# Power-2.net
KiCad netlist of a schematic drawn in Altium Designer
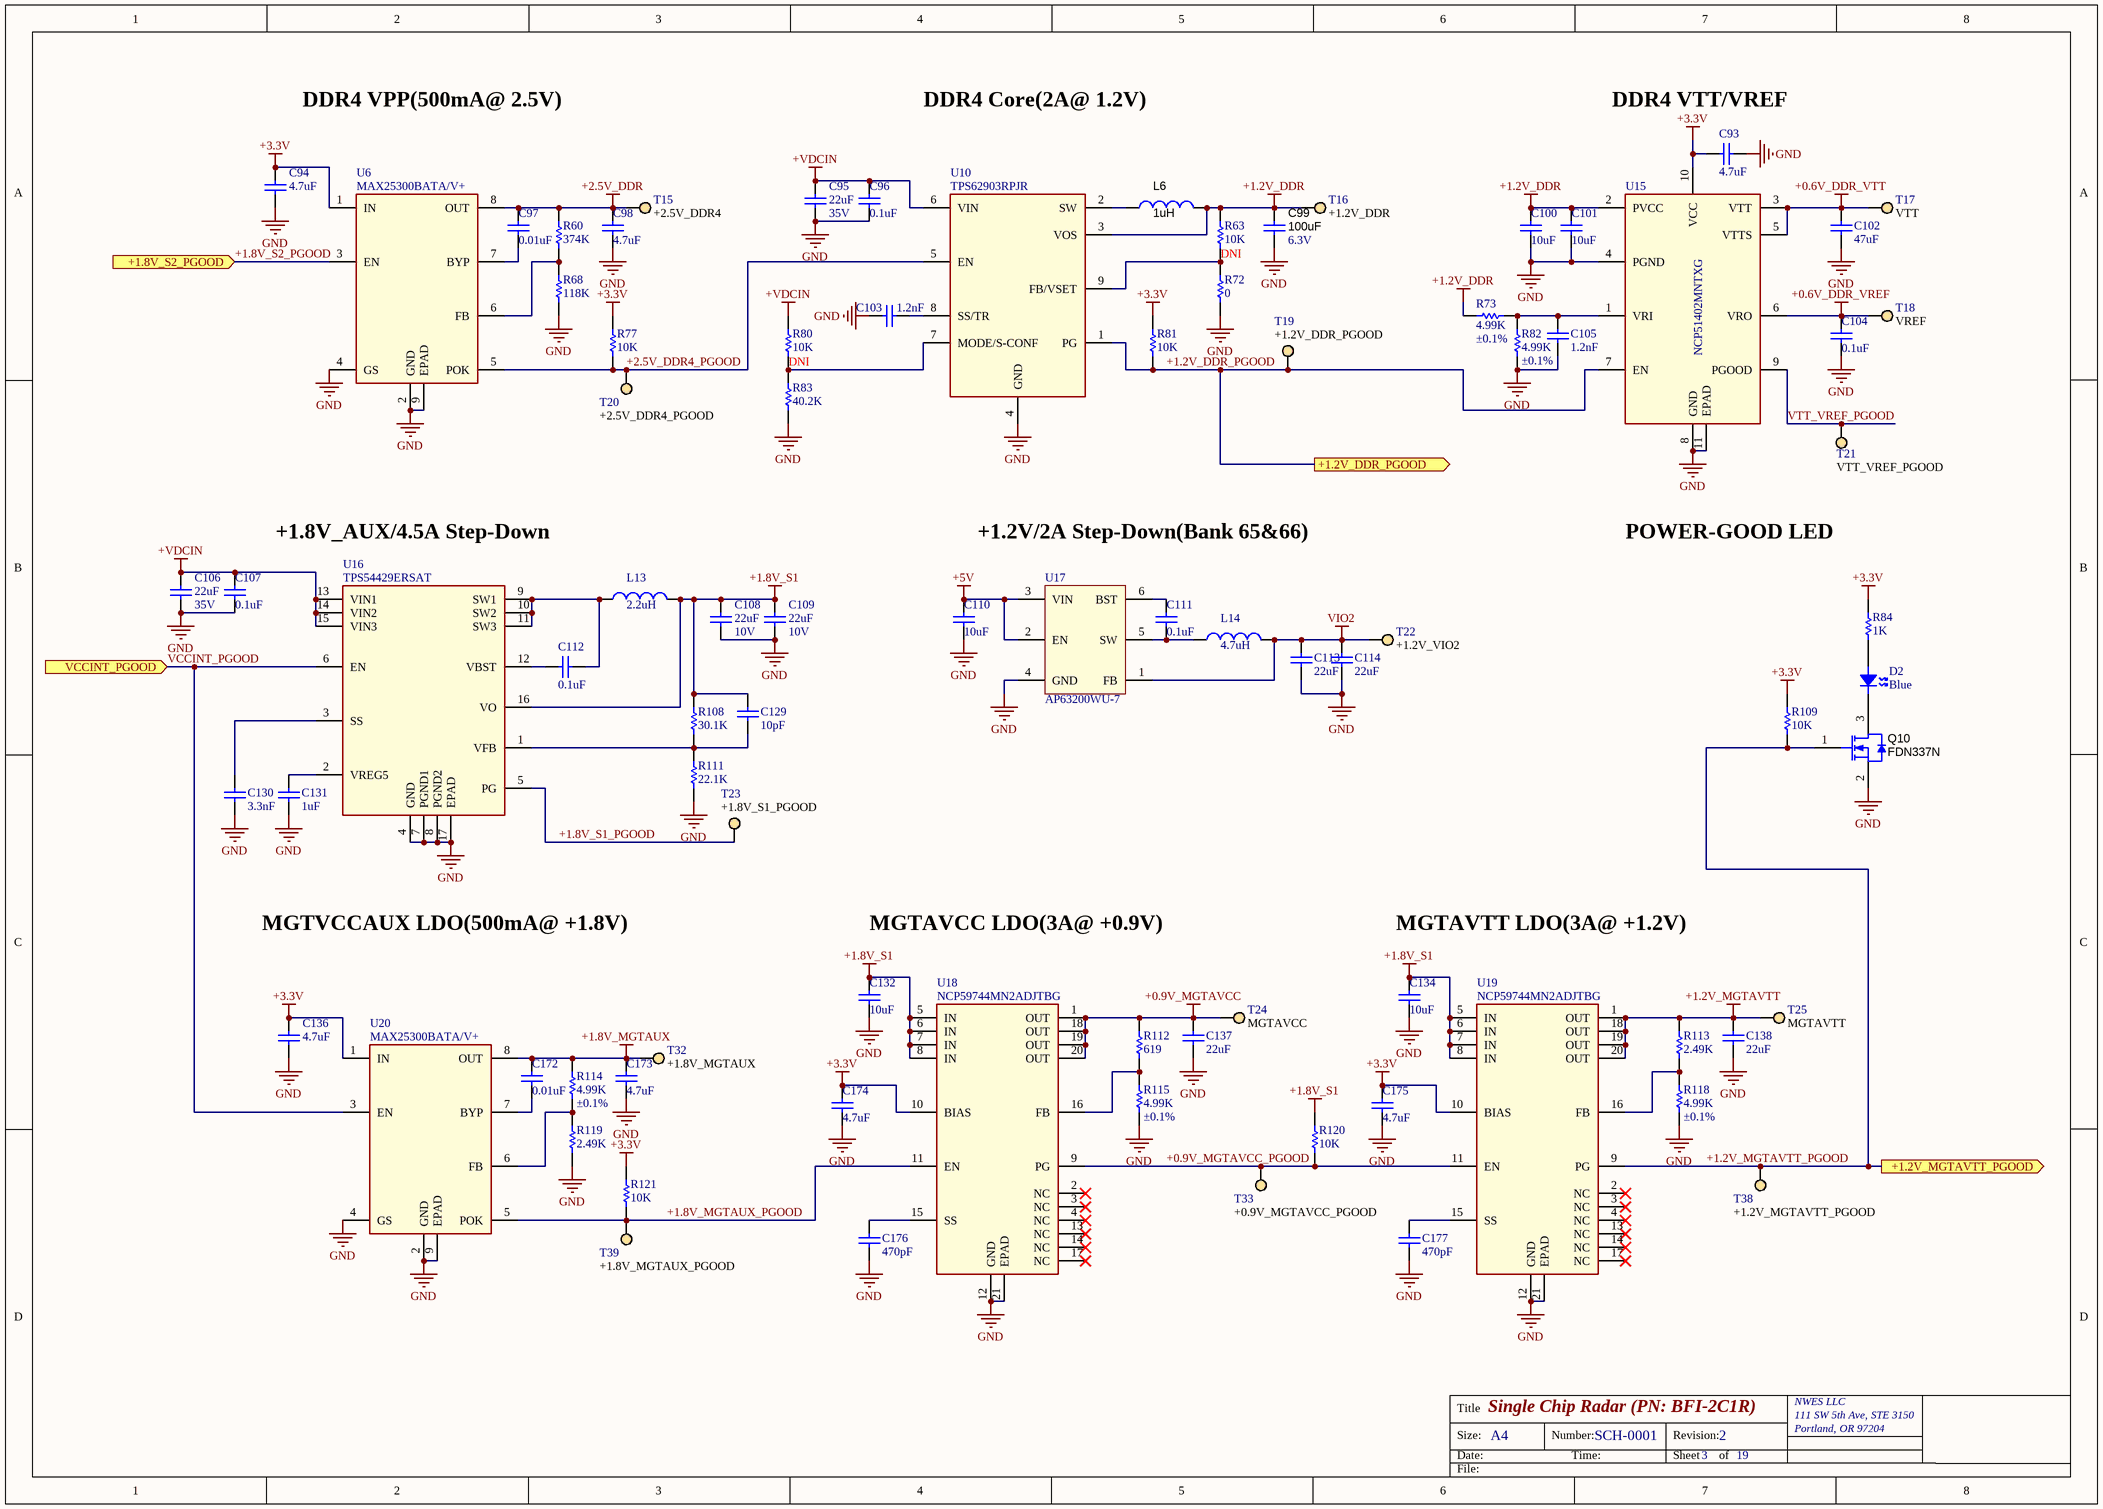
[diagram p0: Power-2.SchDoc]

(export (version "E")
  (design (tool "Eeschema 10.0.6"))
  (components
    (comp (ref "C93")
      (value "4.7uF")
      (footprint "CAPC1005X65USR")
      (description "CAP CER 4.7UF 10V X5R 0402")
      (fields
        (field (name "MANUFACTURER PART NUMBER") "C1005X5R1A475M050BC")
        (field (name "MANUFACTURER") "TDK Corporation")
      )
      (libsource (lib "Radar FPGA RF") (part "CAP CER 4.7UF 10V X5R 0402"))
    )
    (comp (ref "C94")
      (value "4.7uF")
      (footprint "CAPC1005X65USR")
      (description "CAP CER 4.7UF 10V X5R 0402")
      (fields
        (field (name "MANUFACTURER PART NUMBER") "C1005X5R1A475M050BC")
        (field (name "MANUFACTURER") "TDK Corporation")
      )
      (libsource (lib "Radar FPGA RF") (part "CAP CER 4.7UF 10V X5R 0402"))
    )
    (comp (ref "C95")
      (value "22uF")
      (footprint "CAP-1206")
      (description "C Series 1206 22 uF 35 V ±20 % Tolerance X5R SMT Multilayer Ceramic Capacitor")
      (fields
        (field (name "MANUFACTURER") "TDK")
        (field (name "MANUFACTURER PART NUMBER") "C3216X5R1V226M160AC")
        (field (name "VOLTAGE RATING") "35V")
      )
      (libsource (lib "Radar FPGA RF") (part "CAP CER 22UF 35V X5R 1206"))
    )
    (comp (ref "C96")
      (value "0.1uF")
      (footprint "CAPC1005X55USR")
      (description "CAP CER 0.1UF 25V X5R 0402")
      (fields
        (field (name "MANUFACTURER PART NUMBER") "CL05A104KA5NNNC")
        (field (name "MANUFACTURER") "Samsung Electro-Mechanics")
      )
      (libsource (lib "Radar FPGA RF") (part "CAP CER 0.1UF 25V X5R 0402"))
    )
    (comp (ref "C97")
      (value "0.01uF")
      (footprint "CAPC1005X55USR")
      (description "CAP CER 10000PF 50V X7R 0402")
      (fields
        (field (name "MANUFACTURER PART NUMBER") "GCM155R71H103KA55D")
        (field (name "MANUFACTURER") "Murata Electronics")
      )
      (libsource (lib "Radar FPGA RF") (part "CAP CER 0.01uF 50V X7R 0402"))
    )
    (comp (ref "C98")
      (value "4.7uF")
      (footprint "CAPC1005X65USR")
      (description "CAP CER 4.7UF 10V X5R 0402")
      (fields
        (field (name "MANUFACTURER PART NUMBER") "C1005X5R1A475M050BC")
        (field (name "MANUFACTURER") "TDK Corporation")
      )
      (libsource (lib "Radar FPGA RF") (part "CAP CER 4.7UF 10V X5R 0402"))
    )
    (comp (ref "C99")
      (value "100uF")
      (footprint "CAPC3216X180N")
      (description "1206 100 uF 6.3 V ±20% Tolerance X5R SMT Multilayer Ceramic Capacitor")
      (fields
        (field (name "MANUFACTURER") "Murata")
        (field (name "MANUFACTURER PART NUMBER") "GRM31CR60J107ME39L")
        (field (name "VOLTAGE RATING (DC)") "6.3V")
      )
      (libsource (lib "Radar FPGA RF") (part "CAP CER 100UF 6.3V X5R 1206"))
    )
    (comp (ref "C100")
      (value "10uF")
      (footprint "CAPC1005X90")
      (description "CAP CER 10UF 10V X5R 0402")
      (fields
        (field (name "MANUFACTURER PART NUMBER") "CL05A106MP8NUB8")
        (field (name "MANUFACTURER") "Samsung Electro-Mechanics")
      )
      (libsource (lib "Radar FPGA RF") (part "CAP CER 10UF 10V X5R 0402"))
    )
    (comp (ref "C101")
      (value "10uF")
      (footprint "CAPC1005X90")
      (description "CAP CER 10UF 10V X5R 0402")
      (fields
        (field (name "MANUFACTURER PART NUMBER") "CL05A106MP8NUB8")
        (field (name "MANUFACTURER") "Samsung Electro-Mechanics")
      )
      (libsource (lib "Radar FPGA RF") (part "CAP CER 10UF 10V X5R 0402"))
    )
    (comp (ref "C102")
      (value "47uF")
      (footprint "CAP-1206")
      (description "CAP CER 47UF 6.3V X5R 0805")
      (fields
        (field (name "MANUFACTURER") "Samsung")
        (field (name "MANUFACTURER PART NUMBER") "CL21A476MQYNNNE")
      )
      (libsource (lib "Radar FPGA RF") (part "CAP CER 47UF 6.3V X5R 0805"))
    )
    (comp (ref "C103")
      (value "1.2nF")
      (footprint "CAPC1005X55USR")
      (description "0402 1.2 nF 50 V ±10% Tolerance X7R SMT Multilayer Ceramic Capacitor")
      (fields
        (field (name "MANUFACTURER") "Murata")
        (field (name "MANUFACTURER PART NUMBER") "GRM155R71H122KA01D")
      )
      (libsource (lib "Radar FPGA RF") (part "CAP CER 1200PF 50V X7R 0402"))
    )
    (comp (ref "C104")
      (value "0.1uF")
      (footprint "CAPC1005X55USR")
      (description "CAP CER 0.1UF 25V X5R 0402")
      (fields
        (field (name "MANUFACTURER PART NUMBER") "CL05A104KA5NNNC")
        (field (name "MANUFACTURER") "Samsung Electro-Mechanics")
      )
      (libsource (lib "Radar FPGA RF") (part "CAP CER 0.1UF 25V X5R 0402"))
    )
    (comp (ref "C105")
      (value "1.2nF")
      (footprint "CAPC1005X55USR")
      (description "0402 1.2 nF 50 V ±10% Tolerance X7R SMT Multilayer Ceramic Capacitor")
      (fields
        (field (name "MANUFACTURER") "Murata")
        (field (name "MANUFACTURER PART NUMBER") "GRM155R71H122KA01D")
      )
      (libsource (lib "Radar FPGA RF") (part "CAP CER 1200PF 50V X7R 0402"))
    )
    (comp (ref "C106")
      (value "22uF")
      (footprint "CAPC3216X180N")
      (description "C Series 1206 22 uF 35 V ±20 % Tolerance X5R SMT Multilayer Ceramic Capacitor")
      (fields
        (field (name "MANUFACTURER") "TDK")
        (field (name "MANUFACTURER PART NUMBER") "C3216X5R1V226M160AC")
        (field (name "VOLTAGE RATING") "35V")
      )
      (libsource (lib "Radar FPGA RF") (part "CAP CER 22UF 35V X5R 1206"))
    )
    (comp (ref "C107")
      (value "0.1uF")
      (footprint "CAPC1005X55USR")
      (description "CAP CER 0.1UF 25V X5R 0402")
      (fields
        (field (name "MANUFACTURER PART NUMBER") "CL05A104KA5NNNC")
        (field (name "MANUFACTURER") "Samsung Electro-Mechanics")
      )
      (libsource (lib "Radar FPGA RF") (part "CAP CER 0.1UF 25V X5R 0402"))
    )
    (comp (ref "C108")
      (value "22uF")
      (footprint "CAPC1608X100N")
      (description "Multilayer Ceramic Capacitor, 22 uF, 10 V, ± 20%, X5R, 0603 [1608 Metric]")
      (fields
        (field (name "MANUFACTURER") "TDK")
        (field (name "MANUFACTURER PART NUMBER") "C1608X5R1A226M080AC")
        (field (name "VOLTAGE RATING") "10V")
      )
      (libsource (lib "Radar FPGA RF") (part "CAP CER 22UF 10V X5R 0603"))
    )
    (comp (ref "C109")
      (value "22uF")
      (footprint "CAPC1608X100N")
      (description "Multilayer Ceramic Capacitor, 22 uF, 10 V, ± 20%, X5R, 0603 [1608 Metric]")
      (fields
        (field (name "MANUFACTURER") "TDK")
        (field (name "MANUFACTURER PART NUMBER") "C1608X5R1A226M080AC")
        (field (name "VOLTAGE RATING") "10V")
      )
      (libsource (lib "Radar FPGA RF") (part "CAP CER 22UF 10V X5R 0603"))
    )
    (comp (ref "C110")
      (value "10uF")
      (footprint "CAPC1005X90")
      (description "CAP CER 10UF 10V X5R 0402")
      (fields
        (field (name "MANUFACTURER PART NUMBER") "CL05A106MP8NUB8")
        (field (name "MANUFACTURER") "Samsung Electro-Mechanics")
      )
      (libsource (lib "Radar FPGA RF") (part "CAP CER 10UF 10V X5R 0402"))
    )
    (comp (ref "C111")
      (value "0.1uF")
      (footprint "CAPC1005X55USR")
      (description "CAP CER 0.1UF 25V X5R 0402")
      (fields
        (field (name "MANUFACTURER PART NUMBER") "CL05A104KA5NNNC")
        (field (name "MANUFACTURER") "Samsung Electro-Mechanics")
      )
      (libsource (lib "Radar FPGA RF") (part "CAP CER 0.1UF 25V X5R 0402"))
    )
    (comp (ref "C112")
      (value "0.1uF")
      (footprint "CAPC1005X55USR")
      (description "CAP CER 0.1UF 25V X5R 0402")
      (fields
        (field (name "MANUFACTURER PART NUMBER") "CL05A104KA5NNNC")
        (field (name "MANUFACTURER") "Samsung Electro-Mechanics")
      )
      (libsource (lib "Radar FPGA RF") (part "CAP CER 0.1UF 25V X5R 0402"))
    )
    (comp (ref "C113")
      (value "22uF")
      (footprint "CAPC1608X100N")
      (description "Multilayer Ceramic Capacitor, 22 uF, 10 V, ± 20%, X5R, 0603 [1608 Metric]")
      (fields
        (field (name "MANUFACTURER") "TDK")
        (field (name "MANUFACTURER PART NUMBER") "C1608X5R1A226M080AC")
      )
      (libsource (lib "Radar FPGA RF") (part "CAP CER 22UF 10V X5R 0603"))
    )
    (comp (ref "C114")
      (value "22uF")
      (footprint "CAPC1608X100N")
      (description "Multilayer Ceramic Capacitor, 22 uF, 10 V, ± 20%, X5R, 0603 [1608 Metric]")
      (fields
        (field (name "MANUFACTURER") "TDK")
        (field (name "MANUFACTURER PART NUMBER") "C1608X5R1A226M080AC")
      )
      (libsource (lib "Radar FPGA RF") (part "CAP CER 22UF 10V X5R 0603"))
    )
    (comp (ref "C129")
      (value "10pF")
      (footprint "CAPC1005X55USR")
      (description "0402 10 pF 50 V ±5% Tolerance C0G SMT Multilayer Ceramic Capacitor")
      (fields
        (field (name "MANUFACTURER") "Murata")
        (field (name "MANUFACTURER PART NUMBER") "GRM1555C1H100JA01D")
      )
      (libsource (lib "Radar FPGA RF") (part "CAP CER 10PF 50V C0G/NP0 0402"))
    )
    (comp (ref "C130")
      (value "3.3nF")
      (footprint "CAPC1005X55USR")
      (description "0402 3.3 nF 50 V ±10% Tolerance X7R SMT Multilayer Ceramic Capacitor")
      (fields
        (field (name "MANUFACTURER") "Murata")
        (field (name "MANUFACTURER PART NUMBER") "GRM155R71H332KA01D")
      )
      (libsource (lib "Radar FPGA RF") (part "CAP CER 3300PF 50V X7R 0402"))
    )
    (comp (ref "C131")
      (value "1uF")
      (footprint "CAPC1005X55USR")
      (description "CAP CER 1UF 25V X5R 0402")
      (fields
        (field (name "MANUFACTURER PART NUMBER") "GRM155R61E105MA12D")
        (field (name "MANUFACTURER") "Murata Electronics")
      )
      (libsource (lib "Radar FPGA RF") (part "CAP CER 1UF 25V X5R 0402"))
    )
    (comp (ref "C132")
      (value "10uF")
      (footprint "CAPC1005X90")
      (description "CAP CER 10UF 10V X5R 0402")
      (fields
        (field (name "MANUFACTURER PART NUMBER") "CL05A106MP8NUB8")
        (field (name "MANUFACTURER") "Samsung Electro-Mechanics")
      )
      (libsource (lib "Radar FPGA RF") (part "CAP CER 10UF 10V X5R 0402"))
    )
    (comp (ref "C134")
      (value "10uF")
      (footprint "CAPC1005X90")
      (description "CAP CER 10UF 10V X5R 0402")
      (fields
        (field (name "MANUFACTURER PART NUMBER") "CL05A106MP8NUB8")
        (field (name "MANUFACTURER") "Samsung Electro-Mechanics")
      )
      (libsource (lib "Radar FPGA RF") (part "CAP CER 10UF 10V X5R 0402"))
    )
    (comp (ref "C136")
      (value "4.7uF")
      (footprint "CAPC1005X65USR")
      (description "CAP CER 4.7UF 10V X5R 0402")
      (fields
        (field (name "MANUFACTURER PART NUMBER") "C1005X5R1A475M050BC")
        (field (name "MANUFACTURER") "TDK Corporation")
      )
      (libsource (lib "Radar FPGA RF") (part "CAP CER 4.7UF 10V X5R 0402"))
    )
    (comp (ref "C137")
      (value "22uF")
      (footprint "CAPC1608X100N")
      (description "Multilayer Ceramic Capacitor, 22 uF, 10 V, ± 20%, X5R, 0603 [1608 Metric]")
      (fields
        (field (name "MANUFACTURER") "TDK")
        (field (name "MANUFACTURER PART NUMBER") "C1608X5R1A226M080AC")
      )
      (libsource (lib "Radar FPGA RF") (part "CAP CER 22UF 10V X5R 0603"))
    )
    (comp (ref "C138")
      (value "22uF")
      (footprint "CAPC1608X100N")
      (description "Multilayer Ceramic Capacitor, 22 uF, 10 V, ± 20%, X5R, 0603 [1608 Metric]")
      (fields
        (field (name "MANUFACTURER") "TDK")
        (field (name "MANUFACTURER PART NUMBER") "C1608X5R1A226M080AC")
      )
      (libsource (lib "Radar FPGA RF") (part "CAP CER 22UF 10V X5R 0603"))
    )
    (comp (ref "C172")
      (value "0.01uF")
      (footprint "CAPC1005X55USR")
      (description "CAP CER 10000PF 50V X7R 0402")
      (fields
        (field (name "MANUFACTURER PART NUMBER") "GCM155R71H103KA55D")
        (field (name "MANUFACTURER") "Murata Electronics")
      )
      (libsource (lib "Radar FPGA RF") (part "CAP CER 0.01uF 50V X7R 0402"))
    )
    (comp (ref "C173")
      (value "4.7uF")
      (footprint "CAPC1005X65USR")
      (description "CAP CER 4.7UF 10V X5R 0402")
      (fields
        (field (name "MANUFACTURER PART NUMBER") "C1005X5R1A475M050BC")
        (field (name "MANUFACTURER") "TDK Corporation")
      )
      (libsource (lib "Radar FPGA RF") (part "CAP CER 4.7UF 10V X5R 0402"))
    )
    (comp (ref "C174")
      (value "4.7uF")
      (footprint "CAPC1005X65USR")
      (description "CAP CER 4.7UF 10V X5R 0402")
      (fields
        (field (name "MANUFACTURER PART NUMBER") "C1005X5R1A475M050BC")
        (field (name "MANUFACTURER") "TDK Corporation")
      )
      (libsource (lib "Radar FPGA RF") (part "CAP CER 4.7UF 10V X5R 0402"))
    )
    (comp (ref "C175")
      (value "4.7uF")
      (footprint "CAPC1005X65USR")
      (description "CAP CER 4.7UF 10V X5R 0402")
      (fields
        (field (name "MANUFACTURER PART NUMBER") "C1005X5R1A475M050BC")
        (field (name "MANUFACTURER") "TDK Corporation")
      )
      (libsource (lib "Radar FPGA RF") (part "CAP CER 4.7UF 10V X5R 0402"))
    )
    (comp (ref "C176")
      (value "470pF")
      (footprint "CAPC1005X55USR")
      (fields
        (field (name "MANUFACTURER") "Murata")
        (field (name "MANUFACTURER PART NUMBER") "GRM155R71H471KA01D")
        (field (name "TOLERANCE") "10%")
      )
      (libsource (lib "Radar FPGA RF") (part "CAP CER 470PF 50V X7R 0402"))
    )
    (comp (ref "C177")
      (value "470pF")
      (footprint "CAPC1005X55USR")
      (fields
        (field (name "MANUFACTURER") "Murata")
        (field (name "MANUFACTURER PART NUMBER") "GRM155R71H471KA01D")
        (field (name "TOLERANCE") "10%")
      )
      (libsource (lib "Radar FPGA RF") (part "CAP CER 470PF 50V X7R 0402"))
    )
    (comp (ref "D2")
      (value "Blue")
      (footprint "LED_0603")
      (description "LED BLUE CLEAR 0603 SMD")
      (fields
        (field (name "MANUFACTURER") "Vishay Lite-On")
        (field (name "MANUFACTURER PART NUMBER") "LTST-C191TBKT")
      )
      (libsource (lib "Radar FPGA RF") (part "LED BLUE CLEAR CHIP SMD 0603"))
    )
    (comp (ref "L6")
      (value "1uH")
      (footprint "DFE252012P")
      (description "Inductor Power Chip Shielded Wirewound 1uH 20% 1MHz Metal 3.3A 0.04Ohm DCR 1008 T/R")
      (fields
        (field (name "MANUFACTURER") "Murata")
        (field (name "MANUFACTURER PART NUMBER") "DFE252012F-1R0M=P2")
      )
      (libsource (lib "Radar FPGA RF") (part "FIXED IND 1UH 3.3A 40 MOHM SMD"))
    )
    (comp (ref "L13")
      (value "2.2uH")
      (footprint "IND_SPM6530T-2R2M")
      (description "Inductor Power Shielded Wirewound 2.2uH 20% 100KHz Metal 8.2A 19mOhm DCR Blister T/R")
      (fields (field (name "MANUFACTURER") "TDK") (field (name "MANUFACTURER PART NUMBER") "SPM6530T-2R2M"))
      (libsource (lib "Radar FPGA RF") (part "FIXED IND 2.2UH 8.2A 19 MOHM SMD"))
    )
    (comp (ref "L14")
      (value "4.7uH")
      (footprint "DFE252012P")
      (description "FIXED IND 4.7UH 2A 200 MOHM SMD")
      (fields
        (field (name "MANUFACTURER") "Murata")
        (field (name "MANUFACTURER PART NUMBER") "DFE252012P-4R7M=P2")
      )
      (libsource (lib "Radar FPGA RF") (part "FIXED IND 4.7UH 2A 200 MOHM SMD"))
    )
    (comp (ref "Q10")
      (value "FDN337N")
      (footprint "SOT-23")
      (description "MOSFET N-CH 30V 2.2A SSOT3")
      (fields (field (name "MANUFACTURER") "ON Semiconductor / Fairchild"))
      (libsource (lib "Radar FPGA RF") (part "MOSFET N-CH 30V 2.2A SUPERSOT3"))
    )
    (comp (ref "R60")
      (value "374K")
      (footprint "RESC1005X40USR")
      (description "RES 374K OHM 1% 1/16W 0402")
      (fields
        (field (name "MANUFACTURER") "YAGEO")
        (field (name "MANUFACTURER PART NUMBER") "RC0402FR-07374KL")
      )
      (libsource (lib "Radar FPGA RF") (part "RES 374K OHM 1% 1/16W 0402"))
    )
    (comp (ref "R63")
      (value "10K")
      (footprint "RESC1005X40USR")
      (description "RES 10K OHM 1% 1/16W 0402")
      (fields
        (field (name "MANUFACTURER") "YAGEO")
        (field (name "MANUFACTURER PART NUMBER") "RC0402FR-0710KL")
      )
      (libsource (lib "Radar FPGA RF") (part "RES 10K OHM 1% 1/16W 0402"))
    )
    (comp (ref "R68")
      (value "118K")
      (footprint "RESC1005X40USR")
      (description "RES 118K OHM 1% 1/16W 0402")
      (fields
        (field (name "MANUFACTURER") "YAGEO")
        (field (name "MANUFACTURER PART NUMBER") "RC0402FR-07118KL")
      )
      (libsource (lib "Radar FPGA RF") (part "RES 118K OHM 1% 1/16W 0402"))
    )
    (comp (ref "R72")
      (value "0")
      (footprint "RESC1005X40USR")
      (description "RES 0 OHM JUMPER 1/16W 0402")
      (fields
        (field (name "MANUFACTURER") "Yageo")
        (field (name "MANUFACTURER PART NUMBER") "RC0402JR-070RL")
      )
      (libsource (lib "Radar FPGA RF") (part "RES 0 OHM JUMPER 1/16W 0402"))
    )
    (comp (ref "R73")
      (value "4.99K")
      (footprint "RESC1005X40USR")
      (description "RES SMD 4.99KOHM 0.1% 1/16W 0402")
      (fields
        (field (name "MANUFACTURER") "YAGEO")
        (field (name "MANUFACTURER PART NUMBER") "RT0402BRD074K99L")
        (field (name "TOLERANCE") "±0.1%")
      )
      (libsource (lib "Radar FPGA RF") (part "RES 4.99KOHM 0.1% 1/16W 0402"))
    )
    (comp (ref "R77")
      (value "10K")
      (footprint "RESC1005X40USR")
      (description "RES 10K OHM 1% 1/16W 0402")
      (fields
        (field (name "MANUFACTURER") "YAGEO")
        (field (name "MANUFACTURER PART NUMBER") "RC0402FR-0710KL")
      )
      (libsource (lib "Radar FPGA RF") (part "RES 10K OHM 1% 1/16W 0402"))
    )
    (comp (ref "R80")
      (value "10K")
      (footprint "RESC1005X40USR")
      (description "RES 10K OHM 1% 1/16W 0402")
      (fields
        (field (name "MANUFACTURER") "YAGEO")
        (field (name "MANUFACTURER PART NUMBER") "RC0402FR-0710KL")
      )
      (libsource (lib "Radar FPGA RF") (part "RES 10K OHM 1% 1/16W 0402"))
    )
    (comp (ref "R81")
      (value "10K")
      (footprint "RESC1005X40USR")
      (description "RES 10K OHM 1% 1/16W 0402")
      (fields
        (field (name "MANUFACTURER") "YAGEO")
        (field (name "MANUFACTURER PART NUMBER") "RC0402FR-0710KL")
      )
      (libsource (lib "Radar FPGA RF") (part "RES 10K OHM 1% 1/16W 0402"))
    )
    (comp (ref "R82")
      (value "4.99K")
      (footprint "RESC1005X40USR")
      (description "RES SMD 4.99KOHM 0.1% 1/16W 0402")
      (fields
        (field (name "MANUFACTURER") "YAGEO")
        (field (name "MANUFACTURER PART NUMBER") "RT0402BRD074K99L")
        (field (name "TOLERANCE") "±0.1%")
      )
      (libsource (lib "Radar FPGA RF") (part "RES 4.99KOHM 0.1% 1/16W 0402"))
    )
    (comp (ref "R83")
      (value "40.2K")
      (footprint "RESC1005X40USR")
      (description "RES 40.2K OHM 1% 1/16W 0402")
      (fields
        (field (name "MANUFACTURER") "YAGEO")
        (field (name "MANUFACTURER PART NUMBER") "RC0402FR-0740K2L")
      )
      (libsource (lib "Radar FPGA RF") (part "RES 40.2K OHM 1% 1/16W 0402"))
    )
    (comp (ref "R84")
      (value "1K")
      (footprint "RESC1005X40USR")
      (description "RES 1K OHM 1% 1/16W 0402")
      (fields
        (field (name "MANUFACTURER") "YAGEO")
        (field (name "MANUFACTURER PART NUMBER") "RC0402FR-071KL")
      )
      (libsource (lib "Radar FPGA RF") (part "RES 1K OHM 1% 1/16W 0402"))
    )
    (comp (ref "R108")
      (value "30.1K")
      (footprint "RESC1005X40USR")
      (description "RES 30.1K OHM 1% 1/16W 0402")
      (fields
        (field (name "MANUFACTURER") "YAGEO")
        (field (name "MANUFACTURER PART NUMBER") "RC0402FR-0730K1L")
      )
      (libsource (lib "Radar FPGA RF") (part "RES 30.1K OHM 1% 1/16W 0402"))
    )
    (comp (ref "R109")
      (value "10K")
      (footprint "RESC1005X40USR")
      (description "RES 10K OHM 1% 1/16W 0402")
      (fields
        (field (name "MANUFACTURER") "YAGEO")
        (field (name "MANUFACTURER PART NUMBER") "RC0402FR-0710KL")
      )
      (libsource (lib "Radar FPGA RF") (part "RES 10K OHM 1% 1/16W 0402"))
    )
    (comp (ref "R111")
      (value "22.1K")
      (footprint "RESC1005X40USR")
      (description "RES 22.1K OHM 1% 1/16W 0402")
      (fields
        (field (name "MANUFACTURER") "YAGEO")
        (field (name "MANUFACTURER PART NUMBER") "RC0402FR-0722K1L")
      )
      (libsource (lib "Radar FPGA RF") (part "RES 22.1K OHM 1% 1/16W 0402"))
    )
    (comp (ref "R112")
      (value "619")
      (footprint "RESC1005X40USR")
      (description "RES 619 OHM 1% 1/16W 0402")
      (fields
        (field (name "MANUFACTURER") "YAGEO")
        (field (name "MANUFACTURER PART NUMBER") "RC0402FR-07619RL")
      )
      (libsource (lib "Radar FPGA RF") (part "RES 619 OHM 1% 1/16W 0402"))
    )
    (comp (ref "R113")
      (value "2.49K")
      (footprint "RESC1005X40USR")
      (description "RES 2.49K OHM 1% 1/16W 0402")
      (fields
        (field (name "MANUFACTURER") "YAGEO")
        (field (name "MANUFACTURER PART NUMBER") "RC0402FR-072K49L")
      )
      (libsource (lib "Radar FPGA RF") (part "RES 2.49K OHM 1% 1/16W 0402"))
    )
    (comp (ref "R114")
      (value "4.99K")
      (footprint "RESC1005X40USR")
      (description "RES SMD 4.99KOHM 0.1% 1/16W 0402")
      (fields
        (field (name "MANUFACTURER") "YAGEO")
        (field (name "MANUFACTURER PART NUMBER") "RT0402BRD074K99L")
        (field (name "TOLERANCE") "±0.1%")
      )
      (libsource (lib "Radar FPGA RF") (part "RES 4.99KOHM 0.1% 1/16W 0402"))
    )
    (comp (ref "R115")
      (value "4.99K")
      (footprint "RESC1005X40USR")
      (description "RES SMD 4.99KOHM 0.1% 1/16W 0402")
      (fields
        (field (name "MANUFACTURER") "YAGEO")
        (field (name "MANUFACTURER PART NUMBER") "RT0402BRD074K99L")
        (field (name "TOLERANCE") "±0.1%")
      )
      (libsource (lib "Radar FPGA RF") (part "RES 4.99KOHM 0.1% 1/16W 0402"))
    )
    (comp (ref "R118")
      (value "4.99K")
      (footprint "RESC1005X40USR")
      (description "RES SMD 4.99KOHM 0.1% 1/16W 0402")
      (fields
        (field (name "MANUFACTURER") "YAGEO")
        (field (name "MANUFACTURER PART NUMBER") "RT0402BRD074K99L")
        (field (name "TOLERANCE") "±0.1%")
      )
      (libsource (lib "Radar FPGA RF") (part "RES 4.99KOHM 0.1% 1/16W 0402"))
    )
    (comp (ref "R119")
      (value "2.49K")
      (footprint "RESC1005X40USR")
      (description "RES 2.49K OHM 1% 1/16W 0402")
      (fields
        (field (name "MANUFACTURER") "YAGEO")
        (field (name "MANUFACTURER PART NUMBER") "RC0402FR-072K49L")
      )
      (libsource (lib "Radar FPGA RF") (part "RES 2.49K OHM 1% 1/16W 0402"))
    )
    (comp (ref "R120")
      (value "10K")
      (footprint "RESC1005X40USR")
      (description "RES 10K OHM 1% 1/16W 0402")
      (fields
        (field (name "MANUFACTURER") "YAGEO")
        (field (name "MANUFACTURER PART NUMBER") "RC0402FR-0710KL")
      )
      (libsource (lib "Radar FPGA RF") (part "RES 10K OHM 1% 1/16W 0402"))
    )
    (comp (ref "R121")
      (value "10K")
      (footprint "RESC1005X40USR")
      (description "RES 10K OHM 1% 1/16W 0402")
      (fields
        (field (name "MANUFACTURER") "YAGEO")
        (field (name "MANUFACTURER PART NUMBER") "RC0402FR-0710KL")
      )
      (libsource (lib "Radar FPGA RF") (part "RES 10K OHM 1% 1/16W 0402"))
    )
    (comp (ref "T15")
      (value "TP_S")
      (footprint "TP_SM_1MM")
      (description "test point")
      (fields (field (name "PARAMETER 1") "+2.5V_DDR4"))
      (libsource (lib "Radar FPGA RF") (part "Test point PAD"))
    )
    (comp (ref "T16")
      (value "TP_S")
      (footprint "TP_SM_1MM")
      (description "test point")
      (fields (field (name "PARAMETER 1") "+1.2V_DDR"))
      (libsource (lib "Radar FPGA RF") (part "Test point PAD"))
    )
    (comp (ref "T17")
      (value "TP_S")
      (footprint "TP_SM_1MM")
      (description "test point")
      (fields (field (name "PARAMETER 1") "VTT"))
      (libsource (lib "Radar FPGA RF") (part "Test point PAD"))
    )
    (comp (ref "T18")
      (value "TP_S")
      (footprint "TP_SM_1MM")
      (description "test point")
      (fields (field (name "PARAMETER 1") "VREF"))
      (libsource (lib "Radar FPGA RF") (part "Test point PAD"))
    )
    (comp (ref "T19")
      (value "TP_S")
      (footprint "TP_SM_1MM")
      (description "test point")
      (fields (field (name "PARAMETER 1") "+1.2V_DDR_PGOOD"))
      (libsource (lib "Radar FPGA RF") (part "Test point PAD"))
    )
    (comp (ref "T20")
      (value "TP_S")
      (footprint "TP_SM_1MM")
      (description "test point")
      (fields (field (name "PARAMETER 1") "+2.5V_DDR4_PGOOD"))
      (libsource (lib "Radar FPGA RF") (part "Test point PAD"))
    )
    (comp (ref "T21")
      (value "TP_S")
      (footprint "TP_SM_1MM")
      (description "test point")
      (fields (field (name "PARAMETER 1") "VTT_VREF_PGOOD"))
      (libsource (lib "Radar FPGA RF") (part "Test point PAD"))
    )
    (comp (ref "T22")
      (value "TP_S")
      (footprint "TP_SM_1MM")
      (description "test point")
      (fields (field (name "PARAMETER 1") "+1.2V_VIO2"))
      (libsource (lib "Radar FPGA RF") (part "Test point PAD"))
    )
    (comp (ref "T23")
      (value "TP_S")
      (footprint "TP_SM_1MM")
      (description "test point")
      (fields (field (name "PARAMETER 1") "+1.8V_S1_PGOOD"))
      (libsource (lib "Radar FPGA RF") (part "Test point PAD"))
    )
    (comp (ref "T24")
      (value "TP_S")
      (footprint "TP_SM_1MM")
      (description "test point")
      (fields (field (name "PARAMETER 1") "MGTAVCC"))
      (libsource (lib "Radar FPGA RF") (part "Test point PAD"))
    )
    (comp (ref "T25")
      (value "TP_S")
      (footprint "TP_SM_1MM")
      (description "test point")
      (fields (field (name "PARAMETER 1") "MGTAVTT"))
      (libsource (lib "Radar FPGA RF") (part "Test point PAD"))
    )
    (comp (ref "T32")
      (value "TP_S")
      (footprint "TP_SM_1MM")
      (description "test point")
      (fields (field (name "PARAMETER 1") "+1.8V_MGTAUX"))
      (libsource (lib "Radar FPGA RF") (part "Test point PAD"))
    )
    (comp (ref "T33")
      (value "TP_S")
      (footprint "TP_SM_1MM")
      (description "test point")
      (fields (field (name "PARAMETER 1") "+0.9V_MGTAVCC_PGOOD"))
      (libsource (lib "Radar FPGA RF") (part "Test point PAD"))
    )
    (comp (ref "T38")
      (value "TP_S")
      (footprint "TP_SM_1MM")
      (description "test point")
      (fields (field (name "PARAMETER 1") "+1.2V_MGTAVTT_PGOOD"))
      (libsource (lib "Radar FPGA RF") (part "Test point PAD"))
    )
    (comp (ref "T39")
      (value "TP_S")
      (footprint "TP_SM_1MM")
      (description "test point")
      (fields (field (name "PARAMETER 1") "+1.8V_MGTAUX_PGOOD"))
      (libsource (lib "Radar FPGA RF") (part "Test point PAD"))
    )
    (comp (ref "U6")
      (value "MAX25300BATA/V+")
      (footprint "8-TDFN-EP (2x2)")
      (description "Ldo, Adj, 0.6-5.3V, 0.5A, -40 To 125Degc Rohs Compliant: Yes")
      (fields (field (name "MANUFACTURER") "Maxim"))
      (libsource (lib "XEM8320") (part "MAX25300BATA/V+"))
    )
    (comp (ref "U10")
      (value "TPS62903RPJR")
      (footprint "9-VQFN-HR (1.5x2)")
      (description "3-V TO 17-V, 3-A, HIGH-EFFICIENC")
      (fields (field (name "MANUFACTURER") "Texas Instruments"))
      (libsource (lib "XEM8320") (part "TPS62903RPJR"))
    )
    (comp (ref "U15")
      (value "NCP51402MNTXG")
      (footprint "DFN10_3X3_ONS-M")
      (description "3 Amp VTT Termination Regulator DDR1, DDR2, DDR3, LPDDR3, DDR4 No droop, 29deg phase margin")
      (fields (field (name "MANUFACTURER") "ON Semiconductor"))
      (libsource (lib "XEM8320") (part "NCP51402MNTXG"))
    )
    (comp (ref "U16")
      (value "TPS54429ERSAT")
      (footprint "16-QFN (4x4)")
      (description "IC REG BUCK ADJ 4.5A 16QFN")
      (fields (field (name "MANUFACTURER") "Texas Instruments"))
      (libsource (lib "XEM8320") (part "TPS54429ERSAT"))
    )
    (comp (ref "U17")
      (value "AP63200WU-7")
      (footprint "SOT95P280X100-6N")
      (description "AP63200 Series 1.2 V 2 A Adjustable Synchronous Buck Converter - TSOT-26")
      (fields (field (name "MANUFACTURER") "Diodes"))
      (libsource (lib "XEM8320") (part "AP63200WU-7"))
    )
    (comp (ref "U18")
      (value "NCP59744MN2ADJTBG")
      (footprint "20-QFN (5x5)")
      (description "NCP59744 Series 3.6 V 3 A Dual-Rail Very Low-Dropout Linear Regulator - QFN-20")
      (fields (field (name "MANUFACTURER") "ON Semiconductor"))
      (libsource (lib "XEM8320") (part "NCP59744MN2ADJTBG"))
    )
    (comp (ref "U19")
      (value "NCP59744MN2ADJTBG")
      (footprint "20-QFN (5x5)")
      (description "NCP59744 Series 3.6 V 3 A Dual-Rail Very Low-Dropout Linear Regulator - QFN-20")
      (fields (field (name "MANUFACTURER") "ON Semiconductor"))
      (libsource (lib "XEM8320") (part "NCP59744MN2ADJTBG"))
    )
    (comp (ref "U20")
      (value "MAX25300BATA/V+")
      (footprint "8-TDFN-EP (2x2)")
      (description "Ldo, Adj, 0.6-5.3V, 0.5A, -40 To 125Degc Rohs Compliant: Yes")
      (fields (field (name "MANUFACTURER") "Maxim"))
      (libsource (lib "XEM8320") (part "MAX25300BATA/V+"))
    )
  )
  (nets
    (net (code "1") (name "+0.6V_DDR_VREF") (class "Default")
      (node (ref "C104") (pin "2") (pinfunction "2_2") (pintype "passive"))
      (node (ref "T18") (pin "1") (pintype "passive"))
      (node (ref "U15") (pin "6") (pinfunction "VRO_6") (pintype "passive"))
    )
    (net (code "2") (name "+0.6V_DDR_VTT") (class "Default")
      (node (ref "C102") (pin "1") (pinfunction "1_1") (pintype "passive"))
      (node (ref "T17") (pin "1") (pintype "passive"))
      (node (ref "U15") (pin "3") (pinfunction "VTT_3") (pintype "passive"))
      (node (ref "U15") (pin "5") (pinfunction "VTTS_5") (pintype "passive"))
    )
    (net (code "3") (name "+0.9V_MGTAVCC") (class "Default")
      (node (ref "C137") (pin "1") (pinfunction "1_1") (pintype "passive"))
      (node (ref "R112") (pin "2") (pinfunction "2_2") (pintype "passive"))
      (node (ref "T24") (pin "1") (pintype "passive"))
      (node (ref "U18") (pin "1") (pinfunction "OUT_1") (pintype "passive"))
      (node (ref "U18") (pin "18") (pinfunction "OUT_18") (pintype "passive"))
      (node (ref "U18") (pin "19") (pinfunction "OUT_19") (pintype "passive"))
      (node (ref "U18") (pin "20") (pinfunction "OUT_20") (pintype "passive"))
    )
    (net (code "4") (name "+1.2V_DDR") (class "Default")
      (node (ref "C100") (pin "2") (pinfunction "2_2") (pintype "passive"))
      (node (ref "C101") (pin "2") (pinfunction "2_2") (pintype "passive"))
      (node (ref "C99") (pin "1") (pinfunction "1_1") (pintype "passive"))
      (node (ref "L6") (pin "2") (pinfunction "2_2") (pintype "passive"))
      (node (ref "R63") (pin "2") (pinfunction "2_2") (pintype "passive"))
      (node (ref "R73") (pin "2") (pinfunction "2_2") (pintype "passive"))
      (node (ref "T16") (pin "1") (pintype "passive"))
      (node (ref "U10") (pin "3") (pinfunction "VOS_3") (pintype "passive"))
      (node (ref "U15") (pin "2") (pinfunction "PVCC_2") (pintype "passive"))
    )
    (net (code "5") (name "+1.2V_MGTAVTT") (class "Default")
      (node (ref "C138") (pin "1") (pinfunction "1_1") (pintype "passive"))
      (node (ref "R113") (pin "2") (pinfunction "2_2") (pintype "passive"))
      (node (ref "T25") (pin "1") (pintype "passive"))
      (node (ref "U19") (pin "1") (pinfunction "OUT_1") (pintype "passive"))
      (node (ref "U19") (pin "18") (pinfunction "OUT_18") (pintype "passive"))
      (node (ref "U19") (pin "19") (pinfunction "OUT_19") (pintype "passive"))
      (node (ref "U19") (pin "20") (pinfunction "OUT_20") (pintype "passive"))
    )
    (net (code "6") (name "+1.8V_MGTAUX") (class "Default")
      (node (ref "C172") (pin "2") (pinfunction "2_2") (pintype "passive"))
      (node (ref "C173") (pin "2") (pinfunction "2_2") (pintype "passive"))
      (node (ref "R114") (pin "2") (pinfunction "2_2") (pintype "passive"))
      (node (ref "T32") (pin "1") (pintype "passive"))
      (node (ref "U20") (pin "8") (pinfunction "OUT_8") (pintype "passive"))
    )
    (net (code "7") (name "+1.8V_S1") (class "Default")
      (node (ref "C108") (pin "1") (pinfunction "1_1") (pintype "passive"))
      (node (ref "C109") (pin "1") (pinfunction "1_1") (pintype "passive"))
      (node (ref "C129") (pin "2") (pinfunction "2_2") (pintype "passive"))
      (node (ref "C132") (pin "2") (pinfunction "2_2") (pintype "passive"))
      (node (ref "C134") (pin "2") (pinfunction "2_2") (pintype "passive"))
      (node (ref "L13") (pin "2") (pinfunction "2_2") (pintype "passive"))
      (node (ref "R108") (pin "2") (pinfunction "2_2") (pintype "passive"))
      (node (ref "R120") (pin "2") (pinfunction "2_2") (pintype "passive"))
      (node (ref "U16") (pin "16") (pinfunction "VO_16") (pintype "passive"))
      (node (ref "U18") (pin "5") (pinfunction "IN_5") (pintype "passive"))
      (node (ref "U18") (pin "6") (pinfunction "IN_6") (pintype "passive"))
      (node (ref "U18") (pin "7") (pinfunction "IN_7") (pintype "passive"))
      (node (ref "U18") (pin "8") (pinfunction "IN_8") (pintype "passive"))
      (node (ref "U19") (pin "5") (pinfunction "IN_5") (pintype "passive"))
      (node (ref "U19") (pin "6") (pinfunction "IN_6") (pintype "passive"))
      (node (ref "U19") (pin "7") (pinfunction "IN_7") (pintype "passive"))
      (node (ref "U19") (pin "8") (pinfunction "IN_8") (pintype "passive"))
    )
    (net (code "8") (name "+2.5V_DDR") (class "Default")
      (node (ref "C97") (pin "2") (pinfunction "2_2") (pintype "passive"))
      (node (ref "C98") (pin "2") (pinfunction "2_2") (pintype "passive"))
      (node (ref "R60") (pin "2") (pinfunction "2_2") (pintype "passive"))
      (node (ref "T15") (pin "1") (pintype "passive"))
      (node (ref "U6") (pin "8") (pinfunction "OUT_8") (pintype "passive"))
    )
    (net (code "9") (name "+3.3V") (class "Default")
      (node (ref "C136") (pin "2") (pinfunction "2_2") (pintype "passive"))
      (node (ref "C174") (pin "2") (pinfunction "2_2") (pintype "passive"))
      (node (ref "C175") (pin "2") (pinfunction "2_2") (pintype "passive"))
      (node (ref "C93") (pin "2") (pinfunction "2_2") (pintype "passive"))
      (node (ref "C94") (pin "2") (pinfunction "2_2") (pintype "passive"))
      (node (ref "R109") (pin "2") (pinfunction "2_2") (pintype "passive"))
      (node (ref "R121") (pin "2") (pinfunction "2_2") (pintype "passive"))
      (node (ref "R77") (pin "2") (pinfunction "2_2") (pintype "passive"))
      (node (ref "R81") (pin "2") (pinfunction "2_2") (pintype "passive"))
      (node (ref "R84") (pin "2") (pinfunction "2_2") (pintype "passive"))
      (node (ref "U15") (pin "10") (pinfunction "VCC_10") (pintype "passive"))
      (node (ref "U18") (pin "10") (pinfunction "BIAS_10") (pintype "passive"))
      (node (ref "U19") (pin "10") (pinfunction "BIAS_10") (pintype "passive"))
      (node (ref "U20") (pin "1") (pinfunction "IN_1") (pintype "passive"))
      (node (ref "U6") (pin "1") (pinfunction "IN_1") (pintype "passive"))
    )
    (net (code "10") (name "+5V") (class "Default")
      (node (ref "C110") (pin "2") (pinfunction "2_2") (pintype "passive"))
      (node (ref "U17") (pin "2") (pinfunction "EN_2") (pintype "passive"))
      (node (ref "U17") (pin "3") (pinfunction "VIN_3") (pintype "power_in"))
    )
    (net (code "11") (name "+VDCIN") (class "Default")
      (node (ref "C106") (pin "1") (pinfunction "1_1") (pintype "passive"))
      (node (ref "C107") (pin "2") (pinfunction "2_2") (pintype "passive"))
      (node (ref "C95") (pin "1") (pinfunction "1_1") (pintype "passive"))
      (node (ref "C96") (pin "2") (pinfunction "2_2") (pintype "passive"))
      (node (ref "R80") (pin "2") (pinfunction "2_2") (pintype "passive"))
      (node (ref "U10") (pin "6") (pinfunction "VIN_6") (pintype "passive"))
      (node (ref "U16") (pin "13") (pinfunction "VIN1_13") (pintype "passive"))
      (node (ref "U16") (pin "14") (pinfunction "VIN2_14") (pintype "passive"))
      (node (ref "U16") (pin "15") (pinfunction "VIN3_15") (pintype "passive"))
    )
    (net (code "12") (name "/+0.9V_MGTAVCC_PGOOD") (class "Default")
      (node (ref "R120") (pin "1") (pinfunction "1_1") (pintype "passive"))
      (node (ref "T33") (pin "1") (pintype "passive"))
      (node (ref "U18") (pin "9") (pinfunction "PG_9") (pintype "passive"))
      (node (ref "U19") (pin "11") (pinfunction "EN_11") (pintype "passive"))
    )
    (net (code "13") (name "/+1.2V_DDR_PGOOD") (class "Default")
      (node (ref "R81") (pin "1") (pinfunction "1_1") (pintype "passive"))
      (node (ref "T19") (pin "1") (pintype "passive"))
      (node (ref "U10") (pin "1") (pinfunction "PG_1") (pintype "passive"))
      (node (ref "U15") (pin "7") (pinfunction "EN_7") (pintype "passive"))
    )
    (net (code "14") (name "/+1.2V_MGTAVTT_PGOOD") (class "Default")
      (node (ref "Q10") (pin "1") (pinfunction "G_1") (pintype "passive"))
      (node (ref "R109") (pin "1") (pinfunction "1_1") (pintype "passive"))
      (node (ref "T38") (pin "1") (pintype "passive"))
      (node (ref "U19") (pin "9") (pinfunction "PG_9") (pintype "passive"))
    )
    (net (code "15") (name "/+1.8V_MGTAUX_PGOOD") (class "Default")
      (node (ref "R121") (pin "1") (pinfunction "1_1") (pintype "passive"))
      (node (ref "T39") (pin "1") (pintype "passive"))
      (node (ref "U18") (pin "11") (pinfunction "EN_11") (pintype "passive"))
      (node (ref "U20") (pin "5") (pinfunction "POK_5") (pintype "passive"))
    )
    (net (code "16") (name "/+1.8V_S1_PGOOD") (class "Default")
      (node (ref "T23") (pin "1") (pintype "passive"))
      (node (ref "U16") (pin "5") (pinfunction "PG_5") (pintype "passive"))
    )
    (net (code "17") (name "/+1.8V_S2_PGOOD") (class "Default")
      (node (ref "U6") (pin "3") (pinfunction "EN_3") (pintype "passive"))
    )
    (net (code "18") (name "/+2.5V_DDR4_PGOOD") (class "Default")
      (node (ref "R77") (pin "1") (pinfunction "1_1") (pintype "passive"))
      (node (ref "T20") (pin "1") (pintype "passive"))
      (node (ref "U10") (pin "5") (pinfunction "EN_5") (pintype "passive"))
      (node (ref "U6") (pin "5") (pinfunction "POK_5") (pintype "passive"))
    )
    (net (code "19") (name "/VCCINT_PGOOD") (class "Default")
      (node (ref "U16") (pin "6") (pinfunction "EN_6") (pintype "passive"))
      (node (ref "U20") (pin "3") (pinfunction "EN_3") (pintype "passive"))
    )
    (net (code "20") (name "/VTT_VREF_PGOOD") (class "Default")
      (node (ref "T21") (pin "1") (pintype "passive"))
      (node (ref "U15") (pin "9") (pinfunction "PGOOD_9") (pintype "passive"))
    )
    (net (code "21") (name "GND") (class "Default")
      (node (ref "C100") (pin "1") (pinfunction "1_1") (pintype "passive"))
      (node (ref "C101") (pin "1") (pinfunction "1_1") (pintype "passive"))
      (node (ref "C102") (pin "2") (pinfunction "2_2") (pintype "passive"))
      (node (ref "C103") (pin "1") (pinfunction "1_1") (pintype "passive"))
      (node (ref "C104") (pin "1") (pinfunction "1_1") (pintype "passive"))
      (node (ref "C105") (pin "1") (pinfunction "1_1") (pintype "passive"))
      (node (ref "C106") (pin "2") (pinfunction "2_2") (pintype "passive"))
      (node (ref "C107") (pin "1") (pinfunction "1_1") (pintype "passive"))
      (node (ref "C108") (pin "2") (pinfunction "2_2") (pintype "passive"))
      (node (ref "C109") (pin "2") (pinfunction "2_2") (pintype "passive"))
      (node (ref "C110") (pin "1") (pinfunction "1_1") (pintype "passive"))
      (node (ref "C113") (pin "2") (pinfunction "2_2") (pintype "passive"))
      (node (ref "C114") (pin "2") (pinfunction "2_2") (pintype "passive"))
      (node (ref "C130") (pin "1") (pinfunction "1_1") (pintype "passive"))
      (node (ref "C131") (pin "1") (pinfunction "1_1") (pintype "passive"))
      (node (ref "C132") (pin "1") (pinfunction "1_1") (pintype "passive"))
      (node (ref "C134") (pin "1") (pinfunction "1_1") (pintype "passive"))
      (node (ref "C136") (pin "1") (pinfunction "1_1") (pintype "passive"))
      (node (ref "C137") (pin "2") (pinfunction "2_2") (pintype "passive"))
      (node (ref "C138") (pin "2") (pinfunction "2_2") (pintype "passive"))
      (node (ref "C173") (pin "1") (pinfunction "1_1") (pintype "passive"))
      (node (ref "C174") (pin "1") (pinfunction "1_1") (pintype "passive"))
      (node (ref "C175") (pin "1") (pinfunction "1_1") (pintype "passive"))
      (node (ref "C176") (pin "1") (pinfunction "1_1") (pintype "passive"))
      (node (ref "C177") (pin "1") (pinfunction "1_1") (pintype "passive"))
      (node (ref "C93") (pin "1") (pinfunction "1_1") (pintype "passive"))
      (node (ref "C94") (pin "1") (pinfunction "1_1") (pintype "passive"))
      (node (ref "C95") (pin "2") (pinfunction "2_2") (pintype "passive"))
      (node (ref "C96") (pin "1") (pinfunction "1_1") (pintype "passive"))
      (node (ref "C98") (pin "1") (pinfunction "1_1") (pintype "passive"))
      (node (ref "C99") (pin "2") (pinfunction "2_2") (pintype "passive"))
      (node (ref "Q10") (pin "2") (pinfunction "S_2") (pintype "passive"))
      (node (ref "R111") (pin "1") (pinfunction "1_1") (pintype "passive"))
      (node (ref "R115") (pin "1") (pinfunction "1_1") (pintype "passive"))
      (node (ref "R118") (pin "1") (pinfunction "1_1") (pintype "passive"))
      (node (ref "R119") (pin "1") (pinfunction "1_1") (pintype "passive"))
      (node (ref "R68") (pin "1") (pinfunction "1_1") (pintype "passive"))
      (node (ref "R72") (pin "1") (pinfunction "1_1") (pintype "passive"))
      (node (ref "R82") (pin "1") (pinfunction "1_1") (pintype "passive"))
      (node (ref "R83") (pin "1") (pinfunction "1_1") (pintype "passive"))
      (node (ref "U10") (pin "4") (pinfunction "GND_4") (pintype "passive"))
      (node (ref "U15") (pin "11") (pinfunction "EPAD_11") (pintype "passive"))
      (node (ref "U15") (pin "4") (pinfunction "PGND_4") (pintype "passive"))
      (node (ref "U15") (pin "8") (pinfunction "GND_8") (pintype "passive"))
      (node (ref "U16") (pin "17") (pinfunction "EPAD_17") (pintype "passive"))
      (node (ref "U16") (pin "4") (pinfunction "GND_4") (pintype "passive"))
      (node (ref "U16") (pin "7") (pinfunction "PGND1_7") (pintype "passive"))
      (node (ref "U16") (pin "8") (pinfunction "PGND2_8") (pintype "passive"))
      (node (ref "U17") (pin "4") (pinfunction "GND_4") (pintype "passive"))
      (node (ref "U18") (pin "12") (pinfunction "GND_12") (pintype "passive"))
      (node (ref "U18") (pin "21") (pinfunction "EPAD_21") (pintype "passive"))
      (node (ref "U19") (pin "12") (pinfunction "GND_12") (pintype "passive"))
      (node (ref "U19") (pin "21") (pinfunction "EPAD_21") (pintype "passive"))
      (node (ref "U20") (pin "2") (pinfunction "GND_2") (pintype "passive"))
      (node (ref "U20") (pin "4") (pinfunction "GS_4") (pintype "passive"))
      (node (ref "U20") (pin "9") (pinfunction "EPAD_9") (pintype "passive"))
      (node (ref "U6") (pin "2") (pinfunction "GND_2") (pintype "passive"))
      (node (ref "U6") (pin "4") (pinfunction "GS_4") (pintype "passive"))
      (node (ref "U6") (pin "9") (pinfunction "EPAD_9") (pintype "passive"))
    )
    (net (code "22") (name "Net-(D2-A)") (class "Default")
      (node (ref "D2") (pin "1") (pinfunction "A_1") (pintype "passive"))
      (node (ref "R84") (pin "1") (pinfunction "1_1") (pintype "passive"))
    )
    (net (code "23") (name "Net-(D2-K)") (class "Default")
      (node (ref "D2") (pin "2") (pinfunction "K_2") (pintype "passive"))
      (node (ref "Q10") (pin "3") (pinfunction "D_3") (pintype "passive"))
    )
    (net (code "24") (name "Net-(U6-BYP)") (class "Default")
      (node (ref "C97") (pin "1") (pinfunction "1_1") (pintype "passive"))
      (node (ref "U6") (pin "7") (pinfunction "BYP_7") (pintype "passive"))
    )
    (net (code "25") (name "Net-(U6-FB)") (class "Default")
      (node (ref "R60") (pin "1") (pinfunction "1_1") (pintype "passive"))
      (node (ref "R68") (pin "2") (pinfunction "2_2") (pintype "passive"))
      (node (ref "U6") (pin "6") (pinfunction "FB_6") (pintype "passive"))
    )
    (net (code "26") (name "Net-(U10-FB{slash}VSET)") (class "Default")
      (node (ref "R63") (pin "1") (pinfunction "1_1") (pintype "passive"))
      (node (ref "R72") (pin "2") (pinfunction "2_2") (pintype "passive"))
      (node (ref "U10") (pin "9") (pinfunction "FB/VSET_9") (pintype "passive"))
    )
    (net (code "27") (name "Net-(U10-MODE{slash}S-CONF)") (class "Default")
      (node (ref "R80") (pin "1") (pinfunction "1_1") (pintype "passive"))
      (node (ref "R83") (pin "2") (pinfunction "2_2") (pintype "passive"))
      (node (ref "U10") (pin "7") (pinfunction "MODE/S-CONF_7") (pintype "passive"))
    )
    (net (code "28") (name "Net-(U10-SS{slash}TR)") (class "Default")
      (node (ref "C103") (pin "2") (pinfunction "2_2") (pintype "passive"))
      (node (ref "U10") (pin "8") (pinfunction "SS/TR_8") (pintype "passive"))
    )
    (net (code "29") (name "Net-(U10-SW)") (class "Default")
      (node (ref "L6") (pin "1") (pinfunction "1_1") (pintype "passive"))
      (node (ref "U10") (pin "2") (pinfunction "SW_2") (pintype "passive"))
    )
    (net (code "30") (name "Net-(U15-VRI)") (class "Default")
      (node (ref "C105") (pin "2") (pinfunction "2_2") (pintype "passive"))
      (node (ref "R73") (pin "1") (pinfunction "1_1") (pintype "passive"))
      (node (ref "R82") (pin "2") (pinfunction "2_2") (pintype "passive"))
      (node (ref "U15") (pin "1") (pinfunction "VRI_1") (pintype "passive"))
    )
    (net (code "31") (name "Net-(U16-SS)") (class "Default")
      (node (ref "C130") (pin "2") (pinfunction "2_2") (pintype "passive"))
      (node (ref "U16") (pin "3") (pinfunction "SS_3") (pintype "passive"))
    )
    (net (code "32") (name "Net-(U16-SW1)") (class "Default")
      (node (ref "C112") (pin "1") (pinfunction "1_1") (pintype "passive"))
      (node (ref "L13") (pin "1") (pinfunction "1_1") (pintype "passive"))
      (node (ref "U16") (pin "10") (pinfunction "SW2_10") (pintype "passive"))
      (node (ref "U16") (pin "11") (pinfunction "SW3_11") (pintype "passive"))
      (node (ref "U16") (pin "9") (pinfunction "SW1_9") (pintype "passive"))
    )
    (net (code "33") (name "Net-(U16-VBST)") (class "Default")
      (node (ref "C112") (pin "2") (pinfunction "2_2") (pintype "passive"))
      (node (ref "U16") (pin "12") (pinfunction "VBST_12") (pintype "passive"))
    )
    (net (code "34") (name "Net-(U16-VFB)") (class "Default")
      (node (ref "C129") (pin "1") (pinfunction "1_1") (pintype "passive"))
      (node (ref "R108") (pin "1") (pinfunction "1_1") (pintype "passive"))
      (node (ref "R111") (pin "2") (pinfunction "2_2") (pintype "passive"))
      (node (ref "U16") (pin "1") (pinfunction "VFB_1") (pintype "passive"))
    )
    (net (code "35") (name "Net-(U16-VREG5)") (class "Default")
      (node (ref "C131") (pin "2") (pinfunction "2_2") (pintype "passive"))
      (node (ref "U16") (pin "2") (pinfunction "VREG5_2") (pintype "passive"))
    )
    (net (code "36") (name "Net-(U17-BST)") (class "Default")
      (node (ref "C111") (pin "2") (pinfunction "2_2") (pintype "passive"))
      (node (ref "U17") (pin "6") (pinfunction "BST_6") (pintype "passive"))
    )
    (net (code "37") (name "Net-(U17-SW)") (class "Default")
      (node (ref "C111") (pin "1") (pinfunction "1_1") (pintype "passive"))
      (node (ref "L14") (pin "1") (pinfunction "1_1") (pintype "passive"))
      (node (ref "U17") (pin "5") (pinfunction "SW_5") (pintype "passive"))
    )
    (net (code "38") (name "Net-(U18-FB)") (class "Default")
      (node (ref "R112") (pin "1") (pinfunction "1_1") (pintype "passive"))
      (node (ref "R115") (pin "2") (pinfunction "2_2") (pintype "passive"))
      (node (ref "U18") (pin "16") (pinfunction "FB_16") (pintype "passive"))
    )
    (net (code "39") (name "Net-(U18-SS)") (class "Default")
      (node (ref "C176") (pin "2") (pinfunction "2_2") (pintype "passive"))
      (node (ref "U18") (pin "15") (pinfunction "SS_15") (pintype "passive"))
    )
    (net (code "40") (name "Net-(U19-FB)") (class "Default")
      (node (ref "R113") (pin "1") (pinfunction "1_1") (pintype "passive"))
      (node (ref "R118") (pin "2") (pinfunction "2_2") (pintype "passive"))
      (node (ref "U19") (pin "16") (pinfunction "FB_16") (pintype "passive"))
    )
    (net (code "41") (name "Net-(U19-SS)") (class "Default")
      (node (ref "C177") (pin "2") (pinfunction "2_2") (pintype "passive"))
      (node (ref "U19") (pin "15") (pinfunction "SS_15") (pintype "passive"))
    )
    (net (code "42") (name "Net-(U20-BYP)") (class "Default")
      (node (ref "C172") (pin "1") (pinfunction "1_1") (pintype "passive"))
      (node (ref "U20") (pin "7") (pinfunction "BYP_7") (pintype "passive"))
    )
    (net (code "43") (name "Net-(U20-FB)") (class "Default")
      (node (ref "R114") (pin "1") (pinfunction "1_1") (pintype "passive"))
      (node (ref "R119") (pin "2") (pinfunction "2_2") (pintype "passive"))
      (node (ref "U20") (pin "6") (pinfunction "FB_6") (pintype "passive"))
    )
    (net (code "44") (name "VIO2") (class "Default")
      (node (ref "C113") (pin "1") (pinfunction "1_1") (pintype "passive"))
      (node (ref "C114") (pin "1") (pinfunction "1_1") (pintype "passive"))
      (node (ref "L14") (pin "2") (pinfunction "2_2") (pintype "passive"))
      (node (ref "T22") (pin "1") (pintype "passive"))
      (node (ref "U17") (pin "1") (pinfunction "FB_1") (pintype "passive"))
    )
    (net (code "45") (name "unconnected-(U18-NC-Pad2)") (class "Default")
      (node (ref "U18") (pin "2") (pinfunction "NC_2") (pintype "passive+no_connect"))
    )
    (net (code "46") (name "unconnected-(U18-NC-Pad3)") (class "Default")
      (node (ref "U18") (pin "3") (pinfunction "NC_3") (pintype "passive+no_connect"))
    )
    (net (code "47") (name "unconnected-(U18-NC-Pad4)") (class "Default")
      (node (ref "U18") (pin "4") (pinfunction "NC_4") (pintype "passive+no_connect"))
    )
    (net (code "48") (name "unconnected-(U18-NC-Pad13)") (class "Default")
      (node (ref "U18") (pin "13") (pinfunction "NC_13") (pintype "passive+no_connect"))
    )
    (net (code "49") (name "unconnected-(U18-NC-Pad14)") (class "Default")
      (node (ref "U18") (pin "14") (pinfunction "NC_14") (pintype "passive+no_connect"))
    )
    (net (code "50") (name "unconnected-(U18-NC-Pad17)") (class "Default")
      (node (ref "U18") (pin "17") (pinfunction "NC_17") (pintype "passive+no_connect"))
    )
    (net (code "51") (name "unconnected-(U19-NC-Pad2)") (class "Default")
      (node (ref "U19") (pin "2") (pinfunction "NC_2") (pintype "passive+no_connect"))
    )
    (net (code "52") (name "unconnected-(U19-NC-Pad3)") (class "Default")
      (node (ref "U19") (pin "3") (pinfunction "NC_3") (pintype "passive+no_connect"))
    )
    (net (code "53") (name "unconnected-(U19-NC-Pad4)") (class "Default")
      (node (ref "U19") (pin "4") (pinfunction "NC_4") (pintype "passive+no_connect"))
    )
    (net (code "54") (name "unconnected-(U19-NC-Pad13)") (class "Default")
      (node (ref "U19") (pin "13") (pinfunction "NC_13") (pintype "passive+no_connect"))
    )
    (net (code "55") (name "unconnected-(U19-NC-Pad14)") (class "Default")
      (node (ref "U19") (pin "14") (pinfunction "NC_14") (pintype "passive+no_connect"))
    )
    (net (code "56") (name "unconnected-(U19-NC-Pad17)") (class "Default")
      (node (ref "U19") (pin "17") (pinfunction "NC_17") (pintype "passive+no_connect"))
    )
  )
)
